# fall_detection.net
KiCad netlist of a schematic drawn in EAGLE
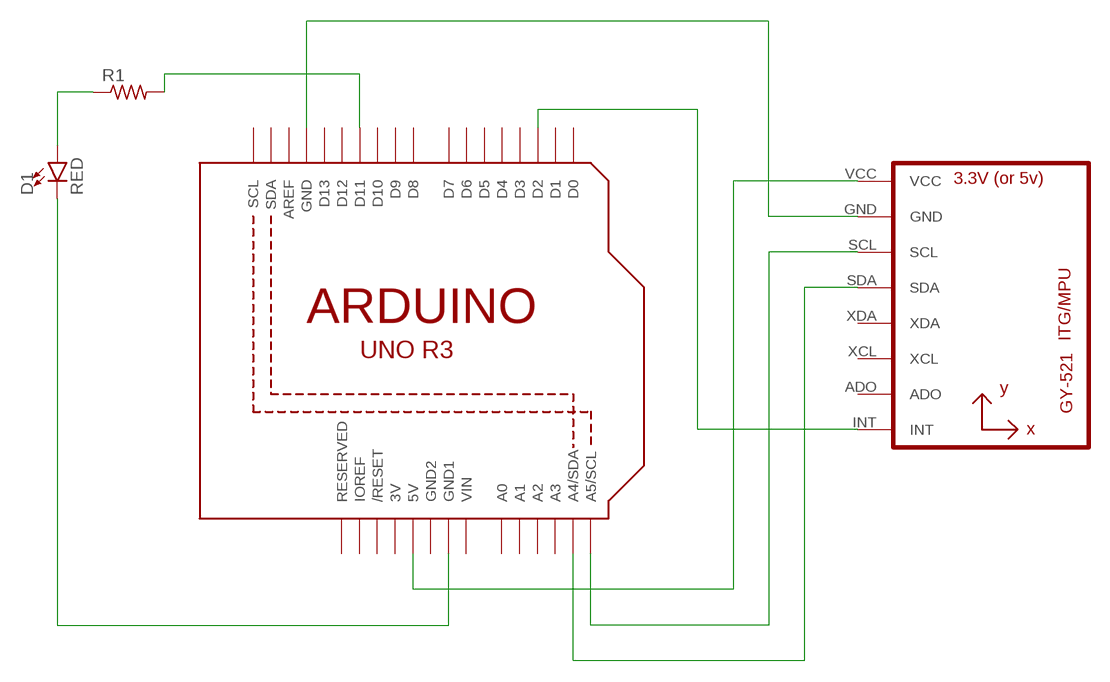
[diagram p0: schematic, sheet 1]

(export (version "E")
  (design (tool "Eeschema 10.0.6"))
  (components
    (comp (ref "D1")
      (value "RED")
      (footprint "eagle-import:LED-0603")
      (libsource (lib "eagle-import") (part "LED-RED0603"))
    )
    (comp (ref "R1")
      (value "R-US_0204/2V")
      (footprint "eagle-import:0204V")
      (libsource (lib "eagle-import") (part "R-US_0204/2V"))
    )
    (comp (ref "U1")
      (value "GY-521MPU6050")
      (footprint "eagle-import:GY-521")
      (libsource (lib "eagle-import") (part "GY-521MPU6050"))
    )
    (comp (ref "U2")
      (value "ARDUINOR3-DIMENSION")
      (footprint "eagle-import:ARDUINOR3")
      (libsource (lib "eagle-import") (part "ARDUINOR3-DIMENSION"))
    )
  )
  (nets
    (net (code "1") (name "/3V") (class "Default")
      (node (ref "U2") (pin "3V") (pinfunction "3V_3V") (pintype "power_in"))
    )
    (net (code "2") (name "/GND2") (class "Default")
      (node (ref "U2") (pin "GND2") (pinfunction "GND2_GND2") (pintype "power_in"))
    )
    (net (code "3") (name "/VIN") (class "Default")
      (node (ref "U2") (pin "VIN") (pinfunction "VIN_VIN") (pintype "power_in"))
    )
    (net (code "4") (name "Net-(D1-PadA)") (class "Default")
      (node (ref "D1") (pin "A") (pinfunction "A_A") (pintype "passive"))
      (node (ref "R1") (pin "1") (pinfunction "1_1") (pintype "passive"))
    )
    (net (code "5") (name "Net-(D1-PadC)") (class "Default")
      (node (ref "D1") (pin "C") (pinfunction "C_C") (pintype "passive"))
      (node (ref "U2") (pin "GND1") (pinfunction "GND1_GND1") (pintype "power_in"))
    )
    (net (code "6") (name "Net-(R1-Pad2)") (class "Default")
      (node (ref "R1") (pin "2") (pinfunction "2_2") (pintype "passive"))
      (node (ref "U2") (pin "D11") (pinfunction "D11_D11") (pintype "bidirectional"))
    )
    (net (code "7") (name "Net-(U1-PadGND)") (class "Default")
      (node (ref "U1") (pin "GND") (pinfunction "GND_GND") (pintype "bidirectional"))
      (node (ref "U2") (pin "GND") (pinfunction "GND_GND") (pintype "power_in"))
    )
    (net (code "8") (name "Net-(U1-PadINT)") (class "Default")
      (node (ref "U1") (pin "INT") (pinfunction "INT_INT") (pintype "bidirectional"))
      (node (ref "U2") (pin "D2") (pinfunction "D2_D2") (pintype "bidirectional"))
    )
    (net (code "9") (name "Net-(U1-PadVCC)") (class "Default")
      (node (ref "U1") (pin "VCC") (pinfunction "VCC_VCC") (pintype "bidirectional"))
      (node (ref "U2") (pin "5V") (pinfunction "5V_5V") (pintype "power_in"))
    )
    (net (code "10") (name "Net-(U2-A4{slash}SDA)") (class "Default")
      (node (ref "U1") (pin "SDA") (pinfunction "SDA_SDA") (pintype "bidirectional"))
      (node (ref "U2") (pin "A4") (pinfunction "A4/SDA_A4") (pintype "bidirectional"))
    )
    (net (code "11") (name "Net-(U2-A5{slash}SCL)") (class "Default")
      (node (ref "U1") (pin "SCL") (pinfunction "SCL_SCL") (pintype "bidirectional"))
      (node (ref "U2") (pin "A5") (pinfunction "A5/SCL_A5") (pintype "bidirectional"))
    )
    (net (code "12") (name "unconnected-(U1-PadADO)") (class "Default")
      (node (ref "U1") (pin "ADO") (pinfunction "ADO_ADO") (pintype "bidirectional"))
    )
    (net (code "13") (name "unconnected-(U1-PadXCL)") (class "Default")
      (node (ref "U1") (pin "XCL") (pinfunction "XCL_XCL") (pintype "bidirectional"))
    )
    (net (code "14") (name "unconnected-(U1-PadXDA)") (class "Default")
      (node (ref "U1") (pin "XDA") (pinfunction "XDA_XDA") (pintype "bidirectional"))
    )
    (net (code "15") (name "unconnected-(U2-PadA0)") (class "Default")
      (node (ref "U2") (pin "A0") (pinfunction "A0_A0") (pintype "bidirectional"))
    )
    (net (code "16") (name "unconnected-(U2-PadA1)") (class "Default")
      (node (ref "U2") (pin "A1") (pinfunction "A1_A1") (pintype "bidirectional"))
    )
    (net (code "17") (name "unconnected-(U2-PadA2)") (class "Default")
      (node (ref "U2") (pin "A2") (pinfunction "A2_A2") (pintype "bidirectional"))
    )
    (net (code "18") (name "unconnected-(U2-PadA3)") (class "Default")
      (node (ref "U2") (pin "A3") (pinfunction "A3_A3") (pintype "bidirectional"))
    )
    (net (code "19") (name "unconnected-(U2-PadAREF)") (class "Default")
      (node (ref "U2") (pin "AREF") (pinfunction "AREF_AREF") (pintype "bidirectional"))
    )
    (net (code "20") (name "unconnected-(U2-PadD0)") (class "Default")
      (node (ref "U2") (pin "D0") (pinfunction "D0_D0") (pintype "bidirectional"))
    )
    (net (code "21") (name "unconnected-(U2-PadD1)") (class "Default")
      (node (ref "U2") (pin "D1") (pinfunction "D1_D1") (pintype "bidirectional"))
    )
    (net (code "22") (name "unconnected-(U2-PadD3)") (class "Default")
      (node (ref "U2") (pin "D3") (pinfunction "D3_D3") (pintype "bidirectional"))
    )
    (net (code "23") (name "unconnected-(U2-PadD4)") (class "Default")
      (node (ref "U2") (pin "D4") (pinfunction "D4_D4") (pintype "bidirectional"))
    )
    (net (code "24") (name "unconnected-(U2-PadD5)") (class "Default")
      (node (ref "U2") (pin "D5") (pinfunction "D5_D5") (pintype "bidirectional"))
    )
    (net (code "25") (name "unconnected-(U2-PadD6)") (class "Default")
      (node (ref "U2") (pin "D6") (pinfunction "D6_D6") (pintype "bidirectional"))
    )
    (net (code "26") (name "unconnected-(U2-PadD7)") (class "Default")
      (node (ref "U2") (pin "D7") (pinfunction "D7_D7") (pintype "bidirectional"))
    )
    (net (code "27") (name "unconnected-(U2-PadD8)") (class "Default")
      (node (ref "U2") (pin "D8") (pinfunction "D8_D8") (pintype "bidirectional"))
    )
    (net (code "28") (name "unconnected-(U2-PadD9)") (class "Default")
      (node (ref "U2") (pin "D9") (pinfunction "D9_D9") (pintype "bidirectional"))
    )
    (net (code "29") (name "unconnected-(U2-PadD10)") (class "Default")
      (node (ref "U2") (pin "D10") (pinfunction "D10_D10") (pintype "bidirectional"))
    )
    (net (code "30") (name "unconnected-(U2-PadD12)") (class "Default")
      (node (ref "U2") (pin "D12") (pinfunction "D12_D12") (pintype "bidirectional"))
    )
    (net (code "31") (name "unconnected-(U2-PadD13)") (class "Default")
      (node (ref "U2") (pin "D13") (pinfunction "D13_D13") (pintype "bidirectional"))
    )
    (net (code "32") (name "unconnected-(U2-PadIOREF)") (class "Default")
      (node (ref "U2") (pin "IOREF") (pinfunction "IOREF_IOREF") (pintype "output"))
    )
    (net (code "33") (name "unconnected-(U2-PadRESERVED)") (class "Default")
      (node (ref "U2") (pin "RESERVED") (pinfunction "RESERVED_RESERVED") (pintype "no_connect"))
    )
    (net (code "34") (name "unconnected-(U2-PadSCL)") (class "Default")
      (node (ref "U2") (pin "SCL") (pinfunction "SCL_SCL") (pintype "bidirectional"))
    )
    (net (code "35") (name "unconnected-(U2-PadSDA)") (class "Default")
      (node (ref "U2") (pin "SDA") (pinfunction "SDA_SDA") (pintype "bidirectional"))
    )
    (net (code "36") (name "unconnected-(U2-{slash}RESET-PadRESET)") (class "Default")
      (node (ref "U2") (pin "RESET") (pinfunction "/RESET_RESET") (pintype "bidirectional"))
    )
  )
)
